# Atmex_1_3.net
KiCad netlist of a schematic drawn in EAGLE
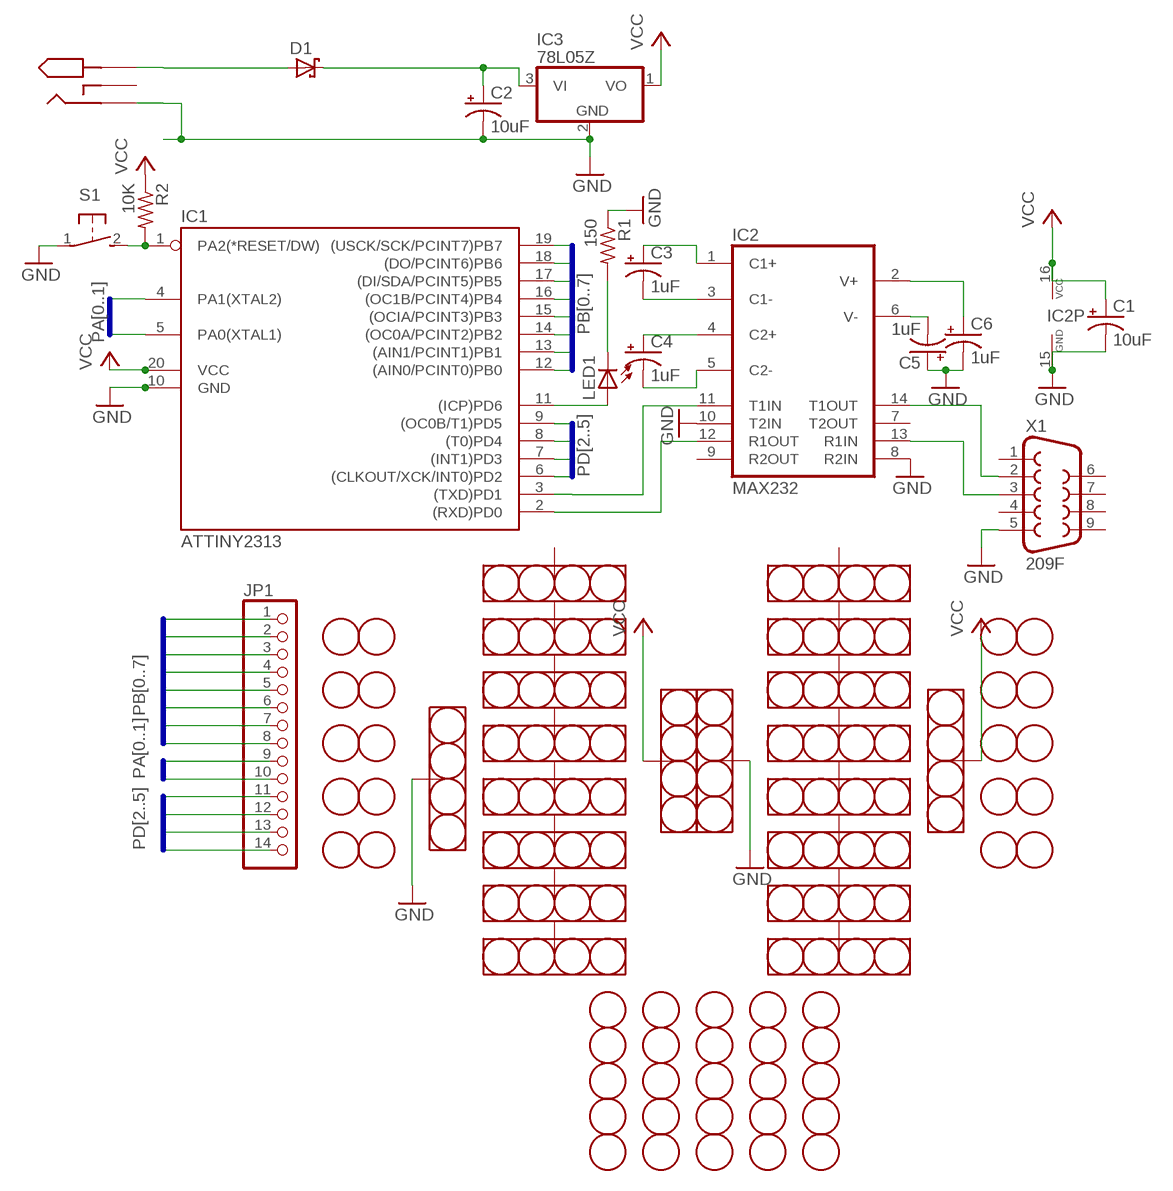
[diagram p0: schematic, sheet 1]

(export (version "E")
  (design (tool "Eeschema 10.0.6"))
  (components
    (comp (ref "C1")
      (value "10uF")
      (footprint "eagle-import:E2-5")
      (libsource (lib "eagle-import") (part "CPOL-USE2-5"))
    )
    (comp (ref "C2")
      (value "10uF")
      (footprint "eagle-import:E2-5")
      (libsource (lib "eagle-import") (part "CPOL-USE2-5"))
    )
    (comp (ref "C3")
      (value "1uF")
      (footprint "eagle-import:E1,8-4")
      (libsource (lib "eagle-import") (part "CPOL-USE1.8-4"))
    )
    (comp (ref "C4")
      (value "1uF")
      (footprint "eagle-import:E1,8-4")
      (libsource (lib "eagle-import") (part "CPOL-USE1.8-4"))
    )
    (comp (ref "C5")
      (value "1uF")
      (footprint "eagle-import:E1,8-4")
      (libsource (lib "eagle-import") (part "CPOL-USE1.8-4"))
    )
    (comp (ref "C6")
      (value "1uF")
      (footprint "eagle-import:E1,8-4")
      (libsource (lib "eagle-import") (part "CPOL-USE1.8-4"))
    )
    (comp (ref "D1")
      (value "SCHOTTKY-DIODEDO35-7")
      (footprint "eagle-import:DO35-7")
      (libsource (lib "eagle-import") (part "SCHOTTKY-DIODEDO35-7"))
    )
    (comp (ref "IC1")
      (value "ATTINY2313")
      (footprint "eagle-import:DIL20")
      (libsource (lib "eagle-import") (part "ATTINY2313"))
    )
    (comp (ref "IC2")
      (value "MAX232")
      (footprint "eagle-import:DIL16")
      (fields (field (name "MF") "MAXIM") (field (name "MPN") "MAX232ACPE+"))
      (libsource (lib "eagle-import") (part "MAX232"))
    )
    (comp (ref "IC3")
      (value "78L05Z")
      (footprint "eagle-import:TO92")
      (libsource (lib "eagle-import") (part "78ZL05"))
    )
    (comp (ref "JP1")
      (value "PINHD-1X14")
      (footprint "eagle-import:1X14")
      (libsource (lib "eagle-import") (part "PINHD-1X14"))
    )
    (comp (ref "LED1")
      (value "LED5MM")
      (footprint "eagle-import:LED5MM")
      (libsource (lib "eagle-import") (part "LED5MM"))
    )
    (comp (ref "R1")
      (value "150")
      (footprint "eagle-import:0204_7")
      (libsource (lib "eagle-import") (part "R-US_0204/7"))
    )
    (comp (ref "R2")
      (value "10K")
      (footprint "eagle-import:0204_7")
      (libsource (lib "eagle-import") (part "R-US_0204/7"))
    )
    (comp (ref "S1")
      (value "31-XX")
      (footprint "eagle-import:B3F-31XX")
      (fields (field (name "MPN") "B3F-3100"))
      (libsource (lib "eagle-import") (part "31-XX"))
    )
    (comp (ref "U$1")
      (value "2.1MMJACK")
      (footprint "eagle-import:PJ-102A")
      (libsource (lib "eagle-import") (part "2.1MMJACK"))
    )
    (comp (ref "U$2")
      (value "PROTOAREAPROTO3")
      (footprint "eagle-import:PROTO_3")
      (libsource (lib "eagle-import") (part "PROTOAREA3"))
    )
    (comp (ref "U$3")
      (value "PROTOAREAPROTO3")
      (footprint "eagle-import:PROTO_3")
      (libsource (lib "eagle-import") (part "PROTOAREA3"))
    )
    (comp (ref "U$4")
      (value "PROTOAREAPROTO3")
      (footprint "eagle-import:PROTO_3")
      (libsource (lib "eagle-import") (part "PROTOAREA3"))
    )
    (comp (ref "U$5")
      (value "PROTOAREAPROTO3")
      (footprint "eagle-import:PROTO_3")
      (libsource (lib "eagle-import") (part "PROTOAREA3"))
    )
    (comp (ref "U$6")
      (value "PROTOAREAPROTO3")
      (footprint "eagle-import:PROTO_3")
      (libsource (lib "eagle-import") (part "PROTOAREA3"))
    )
    (comp (ref "U$7")
      (value "PROTOAREAPROTO3")
      (footprint "eagle-import:PROTO_3")
      (libsource (lib "eagle-import") (part "PROTOAREA3"))
    )
    (comp (ref "U$8")
      (value "PROTOAREAPROTO3")
      (footprint "eagle-import:PROTO_3")
      (libsource (lib "eagle-import") (part "PROTOAREA3"))
    )
    (comp (ref "U$9")
      (value "PROTOAREAPROTO3")
      (footprint "eagle-import:PROTO_3")
      (libsource (lib "eagle-import") (part "PROTOAREA3"))
    )
    (comp (ref "U$10")
      (value "PROTOAREAPROTO3")
      (footprint "eagle-import:PROTO_3")
      (libsource (lib "eagle-import") (part "PROTOAREA3"))
    )
    (comp (ref "U$11")
      (value "PROTOAREAPROTO3")
      (footprint "eagle-import:PROTO_3")
      (libsource (lib "eagle-import") (part "PROTOAREA3"))
    )
    (comp (ref "U$12")
      (value "HEADER12")
      (footprint "eagle-import:HEADER_12")
      (libsource (lib "eagle-import") (part "HEADER12"))
    )
    (comp (ref "U$13")
      (value "HEADER12")
      (footprint "eagle-import:HEADER_12")
      (libsource (lib "eagle-import") (part "HEADER12"))
    )
    (comp (ref "U$14")
      (value "PROTOAREAPROTO3")
      (footprint "eagle-import:PROTO_3")
      (libsource (lib "eagle-import") (part "PROTOAREA3"))
    )
    (comp (ref "U$15")
      (value "PROTOAREAPROTO3")
      (footprint "eagle-import:PROTO_3")
      (libsource (lib "eagle-import") (part "PROTOAREA3"))
    )
    (comp (ref "U$16")
      (value "PROTOAREA")
      (footprint "eagle-import:PROTO_12")
      (libsource (lib "eagle-import") (part "PROTOAREA12"))
    )
    (comp (ref "U$17")
      (value "PROTOAREA")
      (footprint "eagle-import:PROTO_12")
      (libsource (lib "eagle-import") (part "PROTOAREA12"))
    )
    (comp (ref "U$18")
      (value "PROTOAREAPROTO3")
      (footprint "eagle-import:PROTO_3")
      (libsource (lib "eagle-import") (part "PROTOAREA3"))
    )
    (comp (ref "U$19")
      (value "PROTOAREAPROTO3")
      (footprint "eagle-import:PROTO_3")
      (libsource (lib "eagle-import") (part "PROTOAREA3"))
    )
    (comp (ref "U$21")
      (value "PROTOAREAPROTO8")
      (footprint "eagle-import:PROTO_8")
      (libsource (lib "eagle-import") (part "PROTOAREA8"))
    )
    (comp (ref "U$22")
      (value "PROTOAREAPROTO8")
      (footprint "eagle-import:PROTO_8")
      (libsource (lib "eagle-import") (part "PROTOAREA8"))
    )
    (comp (ref "U$23")
      (value "PROTOAREAPROTO3")
      (footprint "eagle-import:PROTO_3")
      (libsource (lib "eagle-import") (part "PROTOAREA3"))
    )
    (comp (ref "U$24")
      (value "PROTOAREAPROTO3")
      (footprint "eagle-import:PROTO_3")
      (libsource (lib "eagle-import") (part "PROTOAREA3"))
    )
    (comp (ref "U$25")
      (value "HEADER12")
      (footprint "eagle-import:HEADER_12")
      (libsource (lib "eagle-import") (part "HEADER12"))
    )
    (comp (ref "U$26")
      (value "HEADER12")
      (footprint "eagle-import:HEADER_12")
      (libsource (lib "eagle-import") (part "HEADER12"))
    )
    (comp (ref "U$27")
      (value "HEADER14")
      (footprint "eagle-import:HEADER_14")
      (libsource (lib "eagle-import") (part "HEADER14"))
    )
    (comp (ref "U$28")
      (value "HEADER8")
      (footprint "eagle-import:HEADER_8")
      (libsource (lib "eagle-import") (part "HEADER8"))
    )
    (comp (ref "U$29")
      (value "HEADER8")
      (footprint "eagle-import:HEADER_8")
      (libsource (lib "eagle-import") (part "HEADER8"))
    )
    (comp (ref "U$30")
      (value "HEADER8")
      (footprint "eagle-import:HEADER_8")
      (libsource (lib "eagle-import") (part "HEADER8"))
    )
    (comp (ref "U$31")
      (value "HEADER8")
      (footprint "eagle-import:HEADER_8")
      (libsource (lib "eagle-import") (part "HEADER8"))
    )
    (comp (ref "X1")
      (value "209F")
      (footprint "eagle-import:F09D")
      (libsource (lib "eagle-import") (part "F09D"))
    )
  )
  (nets
    (net (code "1") (name "/PA0") (class "Default")
      (node (ref "IC1") (pin "5") (pinfunction "PA0(XTAL1)_5") (pintype "bidirectional"))
      (node (ref "JP1") (pin "9") (pinfunction "9_9") (pintype "passive"))
    )
    (net (code "2") (name "/PA1") (class "Default")
      (node (ref "IC1") (pin "4") (pinfunction "PA1(XTAL2)_4") (pintype "bidirectional"))
      (node (ref "JP1") (pin "10") (pinfunction "10_10") (pintype "passive"))
    )
    (net (code "4") (name "/PB0") (class "Default")
      (node (ref "IC1") (pin "12") (pinfunction "(AIN0/PCINT0)PB0_12") (pintype "bidirectional"))
      (node (ref "JP1") (pin "1") (pinfunction "1_1") (pintype "passive"))
    )
    (net (code "5") (name "/PB1") (class "Default")
      (node (ref "IC1") (pin "13") (pinfunction "(AIN1/PCINT1)PB1_13") (pintype "bidirectional"))
      (node (ref "JP1") (pin "2") (pinfunction "2_2") (pintype "passive"))
    )
    (net (code "6") (name "/PB2") (class "Default")
      (node (ref "IC1") (pin "14") (pinfunction "(OC0A/PCINT2)PB2_14") (pintype "bidirectional"))
      (node (ref "JP1") (pin "3") (pinfunction "3_3") (pintype "passive"))
    )
    (net (code "7") (name "/PB3") (class "Default")
      (node (ref "IC1") (pin "15") (pinfunction "(OCIA/PCINT3)PB3_15") (pintype "bidirectional"))
      (node (ref "JP1") (pin "4") (pinfunction "4_4") (pintype "passive"))
    )
    (net (code "8") (name "/PB4") (class "Default")
      (node (ref "IC1") (pin "16") (pinfunction "(OC1B/PCINT4)PB4_16") (pintype "bidirectional"))
      (node (ref "JP1") (pin "5") (pinfunction "5_5") (pintype "passive"))
    )
    (net (code "9") (name "/PB5") (class "Default")
      (node (ref "IC1") (pin "17") (pinfunction "(DI/SDA/PCINT5)PB5_17") (pintype "bidirectional"))
      (node (ref "JP1") (pin "6") (pinfunction "6_6") (pintype "passive"))
    )
    (net (code "10") (name "/PB6") (class "Default")
      (node (ref "IC1") (pin "18") (pinfunction "(DO/PCINT6)PB6_18") (pintype "bidirectional"))
      (node (ref "JP1") (pin "7") (pinfunction "7_7") (pintype "passive"))
    )
    (net (code "11") (name "/PB7") (class "Default")
      (node (ref "IC1") (pin "19") (pinfunction "(USCK/SCK/PCINT7)PB7_19") (pintype "bidirectional"))
      (node (ref "JP1") (pin "8") (pinfunction "8_8") (pintype "passive"))
    )
    (net (code "13") (name "/PD2") (class "Default")
      (node (ref "IC1") (pin "6") (pinfunction "(CLKOUT/XCK/INT0)PD2_6") (pintype "bidirectional"))
      (node (ref "JP1") (pin "11") (pinfunction "11_11") (pintype "passive"))
    )
    (net (code "14") (name "/PD3") (class "Default")
      (node (ref "IC1") (pin "7") (pinfunction "(INT1)PD3_7") (pintype "bidirectional"))
      (node (ref "JP1") (pin "12") (pinfunction "12_12") (pintype "passive"))
    )
    (net (code "15") (name "/PD4") (class "Default")
      (node (ref "IC1") (pin "8") (pinfunction "(T0)PD4_8") (pintype "bidirectional"))
      (node (ref "JP1") (pin "13") (pinfunction "13_13") (pintype "passive"))
    )
    (net (code "16") (name "/PD5") (class "Default")
      (node (ref "IC1") (pin "9") (pinfunction "(OC0B/T1)PD5_9") (pintype "bidirectional"))
      (node (ref "JP1") (pin "14") (pinfunction "14_14") (pintype "passive"))
    )
    (net (code "18") (name "GND") (class "Default")
      (node (ref "C1") (pin "-") (pinfunction "-_-") (pintype "passive"))
      (node (ref "C2") (pin "-") (pinfunction "-_-") (pintype "passive"))
      (node (ref "C5") (pin "+") (pinfunction "+_+") (pintype "passive"))
      (node (ref "C6") (pin "-") (pinfunction "-_-") (pintype "passive"))
      (node (ref "IC1") (pin "10") (pinfunction "GND_10") (pintype "power_in"))
      (node (ref "IC2") (pin "10") (pinfunction "T2IN_10") (pintype "input"))
      (node (ref "IC2") (pin "15") (pinfunction "GND_15") (pintype "power_in"))
      (node (ref "IC2") (pin "8") (pinfunction "R2IN_8") (pintype "input"))
      (node (ref "IC3") (pin "2") (pinfunction "GND_2") (pintype "passive"))
      (node (ref "R1") (pin "1") (pinfunction "1_1") (pintype "passive"))
      (node (ref "S1") (pin "1") (pinfunction "P_1") (pintype "passive"))
      (node (ref "U$1") (pin "R") (pinfunction "R_R") (pintype "bidirectional"))
      (node (ref "U$16") (pin "P$1") (pinfunction "P$1_P$1") (pintype "bidirectional"))
      (node (ref "U$22") (pin "P$1") (pinfunction "P$1_P$1") (pintype "bidirectional"))
      (node (ref "X1") (pin "5") (pinfunction "5_5") (pintype "passive"))
    )
    (net (code "19") (name "Net-(D1-PadA)") (class "Default")
      (node (ref "D1") (pin "A") (pinfunction "A_A") (pintype "passive"))
      (node (ref "U$1") (pin "T") (pinfunction "T_T") (pintype "bidirectional"))
    )
    (net (code "20") (name "Net-(IC1-(ICP)PD6)") (class "Default")
      (node (ref "IC1") (pin "11") (pinfunction "(ICP)PD6_11") (pintype "bidirectional"))
      (node (ref "LED1") (pin "A") (pinfunction "A_A") (pintype "passive"))
    )
    (net (code "21") (name "Net-(IC1-(RXD)PD0)") (class "Default")
      (node (ref "IC1") (pin "2") (pinfunction "(RXD)PD0_2") (pintype "bidirectional"))
      (node (ref "IC2") (pin "12") (pinfunction "R1OUT_12") (pintype "output"))
    )
    (net (code "22") (name "Net-(IC1-(TXD)PD1)") (class "Default")
      (node (ref "IC1") (pin "3") (pinfunction "(TXD)PD1_3") (pintype "bidirectional"))
      (node (ref "IC2") (pin "11") (pinfunction "T1IN_11") (pintype "input"))
    )
    (net (code "23") (name "Net-(IC1-PA2(*RESET{slash}DW))") (class "Default")
      (node (ref "IC1") (pin "1") (pinfunction "PA2(*RESET/DW)_1") (pintype "bidirectional"))
      (node (ref "R2") (pin "2") (pinfunction "2_2") (pintype "passive"))
      (node (ref "S1") (pin "2") (pinfunction "S_2") (pintype "passive"))
    )
    (net (code "24") (name "Net-(IC2A-C1+)") (class "Default")
      (node (ref "C3") (pin "+") (pinfunction "+_+") (pintype "passive"))
      (node (ref "IC2") (pin "1") (pinfunction "C1+_1") (pintype "bidirectional"))
    )
    (net (code "25") (name "Net-(IC2A-C1-)") (class "Default")
      (node (ref "C3") (pin "-") (pinfunction "-_-") (pintype "passive"))
      (node (ref "IC2") (pin "3") (pinfunction "C1-_3") (pintype "bidirectional"))
    )
    (net (code "26") (name "Net-(IC2A-C2+)") (class "Default")
      (node (ref "C4") (pin "+") (pinfunction "+_+") (pintype "passive"))
      (node (ref "IC2") (pin "4") (pinfunction "C2+_4") (pintype "bidirectional"))
    )
    (net (code "27") (name "Net-(IC2A-C2-)") (class "Default")
      (node (ref "C4") (pin "-") (pinfunction "-_-") (pintype "passive"))
      (node (ref "IC2") (pin "5") (pinfunction "C2-_5") (pintype "bidirectional"))
    )
    (net (code "28") (name "Net-(IC2A-R1IN)") (class "Default")
      (node (ref "IC2") (pin "13") (pinfunction "R1IN_13") (pintype "input"))
      (node (ref "X1") (pin "3") (pinfunction "3_3") (pintype "passive"))
    )
    (net (code "29") (name "Net-(IC2A-T1OUT)") (class "Default")
      (node (ref "IC2") (pin "14") (pinfunction "T1OUT_14") (pintype "output"))
      (node (ref "X1") (pin "2") (pinfunction "2_2") (pintype "passive"))
    )
    (net (code "30") (name "Net-(IC2A-V+)") (class "Default")
      (node (ref "C6") (pin "+") (pinfunction "+_+") (pintype "passive"))
      (node (ref "IC2") (pin "2") (pinfunction "V+_2") (pintype "bidirectional"))
    )
    (net (code "31") (name "Net-(IC2A-V-)") (class "Default")
      (node (ref "C5") (pin "-") (pinfunction "-_-") (pintype "passive"))
      (node (ref "IC2") (pin "6") (pinfunction "V-_6") (pintype "bidirectional"))
    )
    (net (code "32") (name "Net-(IC3-VI)") (class "Default")
      (node (ref "C2") (pin "+") (pinfunction "+_+") (pintype "passive"))
      (node (ref "D1") (pin "C") (pinfunction "C_C") (pintype "passive"))
      (node (ref "IC3") (pin "3") (pinfunction "VI_3") (pintype "input"))
    )
    (net (code "33") (name "Net-(LED1-C)") (class "Default")
      (node (ref "LED1") (pin "K") (pinfunction "C_K") (pintype "passive"))
      (node (ref "R1") (pin "2") (pinfunction "2_2") (pintype "passive"))
    )
    (net (code "34") (name "VCC") (class "Default")
      (node (ref "C1") (pin "+") (pinfunction "+_+") (pintype "passive"))
      (node (ref "IC1") (pin "20") (pinfunction "VCC_20") (pintype "power_in"))
      (node (ref "IC2") (pin "16") (pinfunction "VCC_16") (pintype "power_in"))
      (node (ref "IC3") (pin "1") (pinfunction "VO_1") (pintype "passive"))
      (node (ref "R2") (pin "1") (pinfunction "1_1") (pintype "passive"))
      (node (ref "U$17") (pin "P$1") (pinfunction "P$1_P$1") (pintype "bidirectional"))
      (node (ref "U$21") (pin "P$1") (pinfunction "P$1_P$1") (pintype "bidirectional"))
    )
    (net (code "35") (name "unconnected-(IC2A-R2OUT-Pad9)") (class "Default")
      (node (ref "IC2") (pin "9") (pinfunction "R2OUT_9") (pintype "output"))
    )
    (net (code "36") (name "unconnected-(IC2A-T2OUT-Pad7)") (class "Default")
      (node (ref "IC2") (pin "7") (pinfunction "T2OUT_7") (pintype "output"))
    )
    (net (code "37") (name "unconnected-(U$1-PadT_S)") (class "Default")
      (node (ref "U$1") (pin "T_S") (pinfunction "T_S_T_S") (pintype "bidirectional"))
    )
    (net (code "38") (name "unconnected-(U$2-PadP$1)") (class "Default")
      (node (ref "U$2") (pin "P$1") (pinfunction "P$1_P$1") (pintype "bidirectional"))
    )
    (net (code "39") (name "unconnected-(U$3-PadP$1)") (class "Default")
      (node (ref "U$3") (pin "P$1") (pinfunction "P$1_P$1") (pintype "bidirectional"))
    )
    (net (code "40") (name "unconnected-(U$4-PadP$1)") (class "Default")
      (node (ref "U$4") (pin "P$1") (pinfunction "P$1_P$1") (pintype "bidirectional"))
    )
    (net (code "41") (name "unconnected-(U$5-PadP$1)") (class "Default")
      (node (ref "U$5") (pin "P$1") (pinfunction "P$1_P$1") (pintype "bidirectional"))
    )
    (net (code "42") (name "unconnected-(U$6-PadP$1)") (class "Default")
      (node (ref "U$6") (pin "P$1") (pinfunction "P$1_P$1") (pintype "bidirectional"))
    )
    (net (code "43") (name "unconnected-(U$7-PadP$1)") (class "Default")
      (node (ref "U$7") (pin "P$1") (pinfunction "P$1_P$1") (pintype "bidirectional"))
    )
    (net (code "44") (name "unconnected-(U$8-PadP$1)") (class "Default")
      (node (ref "U$8") (pin "P$1") (pinfunction "P$1_P$1") (pintype "bidirectional"))
    )
    (net (code "45") (name "unconnected-(U$9-PadP$1)") (class "Default")
      (node (ref "U$9") (pin "P$1") (pinfunction "P$1_P$1") (pintype "bidirectional"))
    )
    (net (code "46") (name "unconnected-(U$10-PadP$1)") (class "Default")
      (node (ref "U$10") (pin "P$1") (pinfunction "P$1_P$1") (pintype "bidirectional"))
    )
    (net (code "47") (name "unconnected-(U$11-PadP$1)") (class "Default")
      (node (ref "U$11") (pin "P$1") (pinfunction "P$1_P$1") (pintype "bidirectional"))
    )
    (net (code "48") (name "unconnected-(U$14-PadP$1)") (class "Default")
      (node (ref "U$14") (pin "P$1") (pinfunction "P$1_P$1") (pintype "bidirectional"))
    )
    (net (code "49") (name "unconnected-(U$15-PadP$1)") (class "Default")
      (node (ref "U$15") (pin "P$1") (pinfunction "P$1_P$1") (pintype "bidirectional"))
    )
    (net (code "50") (name "unconnected-(U$18-PadP$1)") (class "Default")
      (node (ref "U$18") (pin "P$1") (pinfunction "P$1_P$1") (pintype "bidirectional"))
    )
    (net (code "51") (name "unconnected-(U$19-PadP$1)") (class "Default")
      (node (ref "U$19") (pin "P$1") (pinfunction "P$1_P$1") (pintype "bidirectional"))
    )
    (net (code "52") (name "unconnected-(U$23-PadP$1)") (class "Default")
      (node (ref "U$23") (pin "P$1") (pinfunction "P$1_P$1") (pintype "bidirectional"))
    )
    (net (code "53") (name "unconnected-(U$24-PadP$1)") (class "Default")
      (node (ref "U$24") (pin "P$1") (pinfunction "P$1_P$1") (pintype "bidirectional"))
    )
    (net (code "54") (name "unconnected-(X1-Pad1)") (class "Default")
      (node (ref "X1") (pin "1") (pinfunction "1_1") (pintype "passive"))
    )
    (net (code "55") (name "unconnected-(X1-Pad4)") (class "Default")
      (node (ref "X1") (pin "4") (pinfunction "4_4") (pintype "passive"))
    )
    (net (code "56") (name "unconnected-(X1-Pad6)") (class "Default")
      (node (ref "X1") (pin "6") (pinfunction "6_6") (pintype "passive"))
    )
    (net (code "57") (name "unconnected-(X1-Pad7)") (class "Default")
      (node (ref "X1") (pin "7") (pinfunction "7_7") (pintype "passive"))
    )
    (net (code "58") (name "unconnected-(X1-Pad8)") (class "Default")
      (node (ref "X1") (pin "8") (pinfunction "8_8") (pintype "passive"))
    )
    (net (code "59") (name "unconnected-(X1-Pad9)") (class "Default")
      (node (ref "X1") (pin "9") (pinfunction "9_9") (pintype "passive"))
    )
  )
)
